# WaterDepthAnalysisBoardv2.net
KiCad netlist of a schematic drawn in Altium Designer
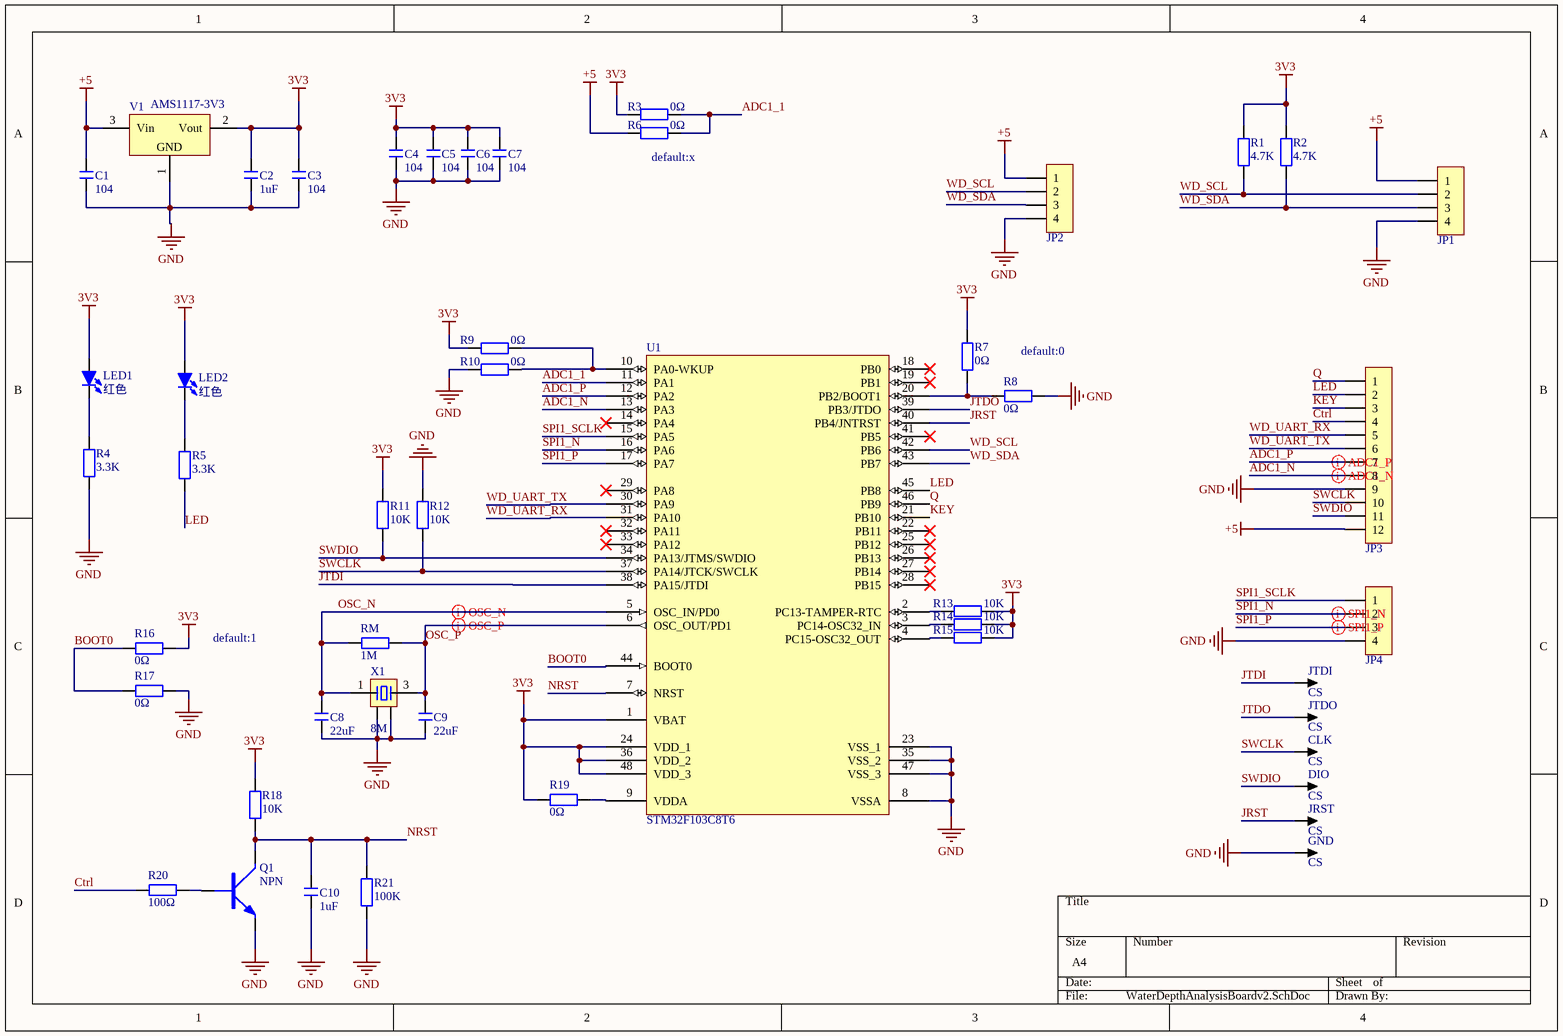
[diagram p0: WaterDepthAnalysisBoardv2.SchDoc]

(export (version "E")
  (design (tool "Eeschema 10.0.6"))
  (components
    (comp (ref "C1")
      (value "104")
      (footprint "C 0603_L")
      (description "无极性贴片电容")
      (fields (field (name "版权归属") "源创客"))
      (libsource (lib "3.1   - 电阻-电容-电感") (part "C"))
    )
    (comp (ref "C2")
      (value "1uF")
      (footprint "C 0603_L")
      (description "无极性贴片电容")
      (fields (field (name "版权归属") "源创客"))
      (libsource (lib "3.1   - 电阻-电容-电感") (part "C"))
    )
    (comp (ref "C3")
      (value "104")
      (footprint "C 0603_L")
      (description "无极性贴片电容")
      (fields (field (name "版权归属") "源创客"))
      (libsource (lib "3.1   - 电阻-电容-电感") (part "C"))
    )
    (comp (ref "C4")
      (value "104")
      (footprint "C 0603_L")
      (description "无极性贴片电容")
      (fields (field (name "版权归属") "源创客"))
      (libsource (lib "3.1   - 电阻-电容-电感") (part "C"))
    )
    (comp (ref "C5")
      (value "104")
      (footprint "C 0603_L")
      (description "无极性贴片电容")
      (fields (field (name "版权归属") "源创客"))
      (libsource (lib "3.1   - 电阻-电容-电感") (part "C"))
    )
    (comp (ref "C6")
      (value "104")
      (footprint "C 0603_L")
      (description "无极性贴片电容")
      (fields (field (name "版权归属") "源创客"))
      (libsource (lib "3.1   - 电阻-电容-电感") (part "C"))
    )
    (comp (ref "C7")
      (value "104")
      (footprint "C 0603_L")
      (description "无极性贴片电容")
      (fields (field (name "版权归属") "源创客"))
      (libsource (lib "3.1   - 电阻-电容-电感") (part "C"))
    )
    (comp (ref "C8")
      (value "22uF")
      (footprint "C 0603_L")
      (description "无极性贴片电容")
      (fields (field (name "版权归属") "源创客"))
      (libsource (lib "3.1   - 电阻-电容-电感") (part "C"))
    )
    (comp (ref "C9")
      (value "22uF")
      (footprint "C 0603_L")
      (description "无极性贴片电容")
      (fields (field (name "版权归属") "源创客"))
      (libsource (lib "3.1   - 电阻-电容-电感") (part "C"))
    )
    (comp (ref "C10")
      (value "1uF")
      (footprint "C 0603_L")
      (description "无极性贴片电容")
      (fields (field (name "版权归属") "源创客"))
      (libsource (lib "3.1   - 电阻-电容-电感") (part "C"))
    )
    (comp (ref "CLK")
      (value "CS")
      (footprint "R100")
      (description "探针焊盘")
      (fields (field (name "版权归属") "源创客"))
      (libsource (lib "15.1 - 未分类器件") (part "CS"))
    )
    (comp (ref "DIO")
      (value "CS")
      (footprint "R100")
      (description "探针焊盘")
      (fields (field (name "版权归属") "源创客"))
      (libsource (lib "15.1 - 未分类器件") (part "CS"))
    )
    (comp (ref "GND")
      (value "CS")
      (footprint "R100")
      (description "探针焊盘")
      (fields (field (name "版权归属") "源创客"))
      (libsource (lib "15.1 - 未分类器件") (part "CS"))
    )
    (comp (ref "JP1")
      (value "HDR-1X4")
      (footprint "MX 1.25-LI-4P")
      (description "4P接插件")
      (fields (field (name "版权归属") "源创客"))
      (libsource (lib "4.2   - 接插件-脚距1.25") (part "Header 4"))
    )
    (comp (ref "JP2")
      (value "HDR-1X4")
      (footprint "MX 1.25-LS-4P")
      (description "4P接插件")
      (fields (field (name "版权归属") "源创客"))
      (libsource (lib "4.2   - 接插件-脚距1.25") (part "Header 4"))
    )
    (comp (ref "JP3")
      (value "HDR-1X12")
      (footprint "HDR2.54-LI-12P")
      (description "12P接插件")
      (fields (field (name "版权归属") "源创客"))
      (libsource (lib "4.5   - 接插件-脚距2.54") (part "Header 12"))
    )
    (comp (ref "JP4")
      (value "HDR-1X4")
      (footprint "HDR2.54-LI-4P")
      (description "4P接插件")
      (fields (field (name "版权归属") "源创客"))
      (libsource (lib "4.5   - 接插件-脚距2.54") (part "Header 4"))
    )
    (comp (ref "JRST")
      (value "CS")
      (footprint "R100")
      (description "探针焊盘")
      (fields (field (name "版权归属") "源创客"))
      (libsource (lib "15.1 - 未分类器件") (part "CS"))
    )
    (comp (ref "JTDI")
      (value "CS")
      (footprint "R100")
      (description "探针焊盘")
      (fields (field (name "版权归属") "源创客"))
      (libsource (lib "15.1 - 未分类器件") (part "CS"))
    )
    (comp (ref "JTDO")
      (value "CS")
      (footprint "R100")
      (description "探针焊盘")
      (fields (field (name "版权归属") "源创客"))
      (libsource (lib "15.1 - 未分类器件") (part "CS"))
    )
    (comp (ref "LED1")
      (value "红色")
      (footprint "LED 0603W")
      (description "贴片LED")
      (fields (field (name "版权归属") "源创客"))
      (libsource (lib "9.1   - LED") (part "LED-SMD"))
    )
    (comp (ref "LED2")
      (value "红色")
      (footprint "LED 0603W")
      (description "贴片LED")
      (fields (field (name "版权归属") "源创客"))
      (libsource (lib "9.1   - LED") (part "LED-SMD"))
    )
    (comp (ref "Q1")
      (value "NPN")
      (footprint "SOT-23")
      (description "NPN三极管")
      (libsource (lib "三极管") (part "NPN"))
    )
    (comp (ref "R1")
      (value "4.7K")
      (footprint "R 0603_L")
      (description "贴片电阻")
      (fields (field (name "版权归属") "源创客"))
      (libsource (lib "3.1   - 电阻-电容-电感") (part "R"))
    )
    (comp (ref "R2")
      (value "4.7K")
      (footprint "R 0603_L")
      (description "贴片电阻")
      (fields (field (name "版权归属") "源创客"))
      (libsource (lib "3.1   - 电阻-电容-电感") (part "R"))
    )
    (comp (ref "R3")
      (value "0Ω")
      (footprint "R 0603_L")
      (description "贴片电阻")
      (fields (field (name "版权归属") "源创客"))
      (libsource (lib "3.1   - 电阻-电容-电感") (part "R"))
    )
    (comp (ref "R4")
      (value "3.3K")
      (footprint "R 0603_L")
      (description "贴片电阻")
      (fields (field (name "版权归属") "源创客"))
      (libsource (lib "3.1   - 电阻-电容-电感") (part "R"))
    )
    (comp (ref "R5")
      (value "3.3K")
      (footprint "R 0603_L")
      (description "贴片电阻")
      (fields (field (name "版权归属") "源创客"))
      (libsource (lib "3.1   - 电阻-电容-电感") (part "R"))
    )
    (comp (ref "R6")
      (value "0Ω")
      (footprint "R 0603_L")
      (description "贴片电阻")
      (fields (field (name "版权归属") "源创客"))
      (libsource (lib "3.1   - 电阻-电容-电感") (part "R"))
    )
    (comp (ref "R7")
      (value "0Ω")
      (footprint "R 0603_L")
      (description "贴片电阻")
      (fields (field (name "版权归属") "源创客"))
      (libsource (lib "3.1   - 电阻-电容-电感") (part "R"))
    )
    (comp (ref "R8")
      (value "0Ω")
      (footprint "R 0603_L")
      (description "贴片电阻")
      (fields (field (name "版权归属") "源创客"))
      (libsource (lib "3.1   - 电阻-电容-电感") (part "R"))
    )
    (comp (ref "R9")
      (value "0Ω")
      (footprint "R 0603_L")
      (description "贴片电阻")
      (fields (field (name "版权归属") "源创客"))
      (libsource (lib "3.1   - 电阻-电容-电感") (part "R"))
    )
    (comp (ref "R10")
      (value "0Ω")
      (footprint "R 0603_L")
      (description "贴片电阻")
      (fields (field (name "版权归属") "源创客"))
      (libsource (lib "3.1   - 电阻-电容-电感") (part "R"))
    )
    (comp (ref "R11")
      (value "10K")
      (footprint "R 0603_L")
      (description "贴片电阻")
      (fields (field (name "版权归属") "源创客"))
      (libsource (lib "3.1   - 电阻-电容-电感") (part "R"))
    )
    (comp (ref "R12")
      (value "10K")
      (footprint "R 0603_L")
      (description "贴片电阻")
      (fields (field (name "版权归属") "源创客"))
      (libsource (lib "3.1   - 电阻-电容-电感") (part "R"))
    )
    (comp (ref "R13")
      (value "10K")
      (footprint "R 0603_L")
      (description "贴片电阻")
      (fields (field (name "版权归属") "源创客"))
      (libsource (lib "3.1   - 电阻-电容-电感") (part "R"))
    )
    (comp (ref "R14")
      (value "10K")
      (footprint "R 0603_L")
      (description "贴片电阻")
      (fields (field (name "版权归属") "源创客"))
      (libsource (lib "3.1   - 电阻-电容-电感") (part "R"))
    )
    (comp (ref "R15")
      (value "10K")
      (footprint "R 0603_L")
      (description "贴片电阻")
      (fields (field (name "版权归属") "源创客"))
      (libsource (lib "3.1   - 电阻-电容-电感") (part "R"))
    )
    (comp (ref "R16")
      (value "0Ω")
      (footprint "R 0603_L")
      (description "贴片电阻")
      (fields (field (name "版权归属") "源创客"))
      (libsource (lib "3.1   - 电阻-电容-电感") (part "R"))
    )
    (comp (ref "R17")
      (value "0Ω")
      (footprint "R 0603_L")
      (description "贴片电阻")
      (fields (field (name "版权归属") "源创客"))
      (libsource (lib "3.1   - 电阻-电容-电感") (part "R"))
    )
    (comp (ref "R18")
      (value "10K")
      (footprint "R 0603_L")
      (description "贴片电阻")
      (fields (field (name "版权归属") "源创客"))
      (libsource (lib "3.1   - 电阻-电容-电感") (part "R"))
    )
    (comp (ref "R19")
      (value "0Ω")
      (footprint "R 0603_L")
      (description "贴片电阻")
      (fields (field (name "版权归属") "源创客"))
      (libsource (lib "3.1   - 电阻-电容-电感") (part "R"))
    )
    (comp (ref "R20")
      (value "100Ω")
      (footprint "R 0603_L")
      (description "贴片电阻")
      (fields (field (name "版权归属") "源创客"))
      (libsource (lib "3.1   - 电阻-电容-电感") (part "R"))
    )
    (comp (ref "R21")
      (value "100K")
      (footprint "R 0603_L")
      (description "贴片电阻")
      (fields (field (name "版权归属") "源创客"))
      (libsource (lib "3.1   - 电阻-电容-电感") (part "R"))
    )
    (comp (ref "RM")
      (value "1M")
      (footprint "R 0603_L")
      (description "贴片电阻")
      (fields (field (name "版权归属") "源创客"))
      (libsource (lib "3.1   - 电阻-电容-电感") (part "R"))
    )
    (comp (ref "U1")
      (value "STM32F103C8T6")
      (footprint "LQFP48 7X7")
      (libsource (lib "STM32系列") (part "STM32F103C8T6"))
    )
    (comp (ref "V1")
      (value "AMS1117-3V3")
      (footprint "SOT89_N")
      (description "三端稳压芯片")
      (fields (field (name "版权归属") "源创客"))
      (libsource (lib "1.3   - 电源类芯片") (part "AMS1117"))
    )
    (comp (ref "X1")
      (value "8M")
      (footprint "OSC 5032-4P")
      (description "4脚无源晶振")
      (fields (field (name "版权归属") "源创客"))
      (libsource (lib "10.1 - 保险丝-晶振") (part "XTAL-4P"))
    )
  )
  (nets
    (net (code "1") (name "+5") (class "Default")
      (node (ref "C1") (pin "2") (pinfunction "2_2") (pintype "passive"))
      (node (ref "JP1") (pin "1") (pinfunction "1_1") (pintype "passive"))
      (node (ref "JP2") (pin "1") (pinfunction "1_1") (pintype "passive"))
      (node (ref "JP3") (pin "12") (pinfunction "12_12") (pintype "passive"))
      (node (ref "R6") (pin "2") (pinfunction "2_2") (pintype "passive"))
      (node (ref "V1") (pin "3") (pinfunction "Vin_3") (pintype "passive"))
    )
    (net (code "2") (name "/ADC1_1") (class "Default")
      (node (ref "R3") (pin "1") (pinfunction "1_1") (pintype "passive"))
      (node (ref "R6") (pin "1") (pinfunction "1_1") (pintype "passive"))
      (node (ref "U1") (pin "11") (pinfunction "PA1_11") (pintype "bidirectional"))
    )
    (net (code "3") (name "/ADC1_N") (class "Default")
      (node (ref "JP3") (pin "8") (pinfunction "8_8") (pintype "passive"))
      (node (ref "U1") (pin "13") (pinfunction "PA3_13") (pintype "bidirectional"))
    )
    (net (code "4") (name "/ADC1_P") (class "Default")
      (node (ref "JP3") (pin "7") (pinfunction "7_7") (pintype "passive"))
      (node (ref "U1") (pin "12") (pinfunction "PA2_12") (pintype "bidirectional"))
    )
    (net (code "5") (name "/BOOT0") (class "Default")
      (node (ref "R16") (pin "2") (pinfunction "2_2") (pintype "passive"))
      (node (ref "R17") (pin "2") (pinfunction "2_2") (pintype "passive"))
      (node (ref "U1") (pin "44") (pinfunction "BOOT0_44") (pintype "input"))
    )
    (net (code "6") (name "/Ctrl") (class "Default")
      (node (ref "JP3") (pin "4") (pinfunction "4_4") (pintype "passive"))
      (node (ref "R20") (pin "2") (pinfunction "2_2") (pintype "passive"))
    )
    (net (code "7") (name "/JRST") (class "Default")
      (node (ref "JRST") (pin "1") (pinfunction "1_1") (pintype "passive"))
      (node (ref "U1") (pin "40") (pinfunction "PB4/JNTRST_40") (pintype "bidirectional"))
    )
    (net (code "8") (name "/JTDI") (class "Default")
      (node (ref "JTDI") (pin "1") (pinfunction "1_1") (pintype "passive"))
      (node (ref "U1") (pin "38") (pinfunction "PA15/JTDI_38") (pintype "bidirectional"))
    )
    (net (code "9") (name "/JTDO") (class "Default")
      (node (ref "JTDO") (pin "1") (pinfunction "1_1") (pintype "passive"))
      (node (ref "U1") (pin "39") (pinfunction "PB3/JTDO_39") (pintype "bidirectional"))
    )
    (net (code "10") (name "/KEY") (class "Default")
      (node (ref "JP3") (pin "3") (pinfunction "3_3") (pintype "passive"))
      (node (ref "U1") (pin "21") (pinfunction "PB10_21") (pintype "bidirectional"))
    )
    (net (code "11") (name "/LED") (class "Default")
      (node (ref "JP3") (pin "2") (pinfunction "2_2") (pintype "passive"))
      (node (ref "R5") (pin "1") (pinfunction "1_1") (pintype "passive"))
      (node (ref "U1") (pin "45") (pinfunction "PB8_45") (pintype "bidirectional"))
    )
    (net (code "12") (name "/NRST") (class "Default")
      (node (ref "C10") (pin "2") (pinfunction "2_2") (pintype "passive"))
      (node (ref "Q1") (pin "C") (pinfunction "C_C") (pintype "passive"))
      (node (ref "R18") (pin "2") (pinfunction "2_2") (pintype "passive"))
      (node (ref "R21") (pin "1") (pinfunction "1_1") (pintype "passive"))
      (node (ref "U1") (pin "7") (pinfunction "NRST_7") (pintype "bidirectional"))
    )
    (net (code "13") (name "/OSC_N") (class "Default")
      (node (ref "C8") (pin "2") (pinfunction "2_2") (pintype "passive"))
      (node (ref "RM") (pin "2") (pinfunction "2_2") (pintype "passive"))
      (node (ref "U1") (pin "5") (pinfunction "OSC_IN/PD0_5") (pintype "input"))
      (node (ref "X1") (pin "1") (pinfunction "1_1") (pintype "passive"))
    )
    (net (code "14") (name "/OSC_P") (class "Default")
      (node (ref "C9") (pin "2") (pinfunction "2_2") (pintype "passive"))
      (node (ref "RM") (pin "1") (pinfunction "1_1") (pintype "passive"))
      (node (ref "U1") (pin "6") (pinfunction "OSC_OUT/PD1_6") (pintype "output"))
      (node (ref "X1") (pin "3") (pinfunction "3_3") (pintype "passive"))
    )
    (net (code "15") (name "/Q") (class "Default")
      (node (ref "JP3") (pin "1") (pinfunction "1_1") (pintype "passive"))
      (node (ref "U1") (pin "46") (pinfunction "PB9_46") (pintype "bidirectional"))
    )
    (net (code "16") (name "/SPI1_N") (class "Default")
      (node (ref "JP4") (pin "2") (pinfunction "2_2") (pintype "passive"))
      (node (ref "U1") (pin "16") (pinfunction "PA6_16") (pintype "bidirectional"))
    )
    (net (code "17") (name "/SPI1_P") (class "Default")
      (node (ref "JP4") (pin "3") (pinfunction "3_3") (pintype "passive"))
      (node (ref "U1") (pin "17") (pinfunction "PA7_17") (pintype "bidirectional"))
    )
    (net (code "18") (name "/SPI1_SCLK") (class "Default")
      (node (ref "JP4") (pin "1") (pinfunction "1_1") (pintype "passive"))
      (node (ref "U1") (pin "15") (pinfunction "PA5_15") (pintype "bidirectional"))
    )
    (net (code "19") (name "/SWCLK") (class "Default")
      (node (ref "CLK") (pin "1") (pinfunction "1_1") (pintype "passive"))
      (node (ref "JP3") (pin "10") (pinfunction "10_10") (pintype "passive"))
      (node (ref "R12") (pin "2") (pinfunction "2_2") (pintype "passive"))
      (node (ref "U1") (pin "37") (pinfunction "PA14/JTCK/SWCLK_37") (pintype "bidirectional"))
    )
    (net (code "20") (name "/SWDIO") (class "Default")
      (node (ref "DIO") (pin "1") (pinfunction "1_1") (pintype "passive"))
      (node (ref "JP3") (pin "11") (pinfunction "11_11") (pintype "passive"))
      (node (ref "R11") (pin "2") (pinfunction "2_2") (pintype "passive"))
      (node (ref "U1") (pin "34") (pinfunction "PA13/JTMS/SWDIO_34") (pintype "bidirectional"))
    )
    (net (code "21") (name "/WD_SCL") (class "Default")
      (node (ref "JP1") (pin "2") (pinfunction "2_2") (pintype "passive"))
      (node (ref "JP2") (pin "2") (pinfunction "2_2") (pintype "passive"))
      (node (ref "R1") (pin "1") (pinfunction "1_1") (pintype "passive"))
      (node (ref "U1") (pin "42") (pinfunction "PB6_42") (pintype "bidirectional"))
    )
    (net (code "22") (name "/WD_SDA") (class "Default")
      (node (ref "JP1") (pin "3") (pinfunction "3_3") (pintype "passive"))
      (node (ref "JP2") (pin "3") (pinfunction "3_3") (pintype "passive"))
      (node (ref "R2") (pin "1") (pinfunction "1_1") (pintype "passive"))
      (node (ref "U1") (pin "43") (pinfunction "PB7_43") (pintype "bidirectional"))
    )
    (net (code "23") (name "/WD_UART_RX") (class "Default")
      (node (ref "JP3") (pin "5") (pinfunction "5_5") (pintype "passive"))
      (node (ref "U1") (pin "31") (pinfunction "PA10_31") (pintype "bidirectional"))
    )
    (net (code "24") (name "/WD_UART_TX") (class "Default")
      (node (ref "JP3") (pin "6") (pinfunction "6_6") (pintype "passive"))
      (node (ref "U1") (pin "30") (pinfunction "PA9_30") (pintype "bidirectional"))
    )
    (net (code "25") (name "3V3") (class "Default")
      (node (ref "C2") (pin "2") (pinfunction "2_2") (pintype "passive"))
      (node (ref "C3") (pin "2") (pinfunction "2_2") (pintype "passive"))
      (node (ref "C4") (pin "2") (pinfunction "2_2") (pintype "passive"))
      (node (ref "C5") (pin "2") (pinfunction "2_2") (pintype "passive"))
      (node (ref "C6") (pin "2") (pinfunction "2_2") (pintype "passive"))
      (node (ref "C7") (pin "2") (pinfunction "2_2") (pintype "passive"))
      (node (ref "LED1") (pin "1") (pinfunction "A_1") (pintype "passive"))
      (node (ref "LED2") (pin "1") (pinfunction "A_1") (pintype "passive"))
      (node (ref "R1") (pin "2") (pinfunction "2_2") (pintype "passive"))
      (node (ref "R11") (pin "1") (pinfunction "1_1") (pintype "passive"))
      (node (ref "R13") (pin "1") (pinfunction "1_1") (pintype "passive"))
      (node (ref "R14") (pin "1") (pinfunction "1_1") (pintype "passive"))
      (node (ref "R15") (pin "1") (pinfunction "1_1") (pintype "passive"))
      (node (ref "R16") (pin "1") (pinfunction "1_1") (pintype "passive"))
      (node (ref "R18") (pin "1") (pinfunction "1_1") (pintype "passive"))
      (node (ref "R19") (pin "2") (pinfunction "2_2") (pintype "passive"))
      (node (ref "R2") (pin "2") (pinfunction "2_2") (pintype "passive"))
      (node (ref "R3") (pin "2") (pinfunction "2_2") (pintype "passive"))
      (node (ref "R7") (pin "1") (pinfunction "1_1") (pintype "passive"))
      (node (ref "R9") (pin "2") (pinfunction "2_2") (pintype "passive"))
      (node (ref "U1") (pin "1") (pinfunction "VBAT_1") (pintype "power_in"))
      (node (ref "U1") (pin "24") (pinfunction "VDD_1_24") (pintype "power_in"))
      (node (ref "U1") (pin "36") (pinfunction "VDD_2_36") (pintype "power_in"))
      (node (ref "U1") (pin "48") (pinfunction "VDD_3_48") (pintype "power_in"))
      (node (ref "V1") (pin "2") (pinfunction "Vout_2") (pintype "passive"))
    )
    (net (code "26") (name "GND") (class "Default")
      (node (ref "C1") (pin "1") (pinfunction "1_1") (pintype "passive"))
      (node (ref "C10") (pin "1") (pinfunction "1_1") (pintype "passive"))
      (node (ref "C2") (pin "1") (pinfunction "1_1") (pintype "passive"))
      (node (ref "C3") (pin "1") (pinfunction "1_1") (pintype "passive"))
      (node (ref "C4") (pin "1") (pinfunction "1_1") (pintype "passive"))
      (node (ref "C5") (pin "1") (pinfunction "1_1") (pintype "passive"))
      (node (ref "C6") (pin "1") (pinfunction "1_1") (pintype "passive"))
      (node (ref "C7") (pin "1") (pinfunction "1_1") (pintype "passive"))
      (node (ref "C8") (pin "1") (pinfunction "1_1") (pintype "passive"))
      (node (ref "C9") (pin "1") (pinfunction "1_1") (pintype "passive"))
      (node (ref "GND") (pin "1") (pinfunction "1_1") (pintype "passive"))
      (node (ref "JP1") (pin "4") (pinfunction "4_4") (pintype "passive"))
      (node (ref "JP2") (pin "4") (pinfunction "4_4") (pintype "passive"))
      (node (ref "JP3") (pin "9") (pinfunction "9_9") (pintype "passive"))
      (node (ref "JP4") (pin "4") (pinfunction "4_4") (pintype "passive"))
      (node (ref "Q1") (pin "E") (pinfunction "E_E") (pintype "passive"))
      (node (ref "R10") (pin "2") (pinfunction "2_2") (pintype "passive"))
      (node (ref "R12") (pin "1") (pinfunction "1_1") (pintype "passive"))
      (node (ref "R17") (pin "1") (pinfunction "1_1") (pintype "passive"))
      (node (ref "R21") (pin "2") (pinfunction "2_2") (pintype "passive"))
      (node (ref "R4") (pin "1") (pinfunction "1_1") (pintype "passive"))
      (node (ref "R8") (pin "1") (pinfunction "1_1") (pintype "passive"))
      (node (ref "U1") (pin "23") (pinfunction "VSS_1_23") (pintype "power_in"))
      (node (ref "U1") (pin "35") (pinfunction "VSS_2_35") (pintype "power_in"))
      (node (ref "U1") (pin "47") (pinfunction "VSS_3_47") (pintype "power_in"))
      (node (ref "U1") (pin "8") (pinfunction "VSSA_8") (pintype "power_in"))
      (node (ref "V1") (pin "1") (pinfunction "GND_1") (pintype "passive"))
      (node (ref "X1") (pin "2") (pinfunction "2_2") (pintype "passive"))
      (node (ref "X1") (pin "4") (pinfunction "4_4") (pintype "passive"))
    )
    (net (code "27") (name "Net-(LED1-K)") (class "Default")
      (node (ref "LED1") (pin "2") (pinfunction "K_2") (pintype "passive"))
      (node (ref "R4") (pin "2") (pinfunction "2_2") (pintype "passive"))
    )
    (net (code "28") (name "Net-(LED2-K)") (class "Default")
      (node (ref "LED2") (pin "2") (pinfunction "K_2") (pintype "passive"))
      (node (ref "R5") (pin "2") (pinfunction "2_2") (pintype "passive"))
    )
    (net (code "29") (name "Net-(Q1-PadB)") (class "Default")
      (node (ref "Q1") (pin "B") (pinfunction "B_B") (pintype "passive"))
      (node (ref "R20") (pin "1") (pinfunction "1_1") (pintype "passive"))
    )
    (net (code "30") (name "Net-(U1-PA0-WKUP)") (class "Default")
      (node (ref "R10") (pin "1") (pinfunction "1_1") (pintype "passive"))
      (node (ref "R9") (pin "1") (pinfunction "1_1") (pintype "passive"))
      (node (ref "U1") (pin "10") (pinfunction "PA0-WKUP_10") (pintype "bidirectional"))
    )
    (net (code "31") (name "Net-(U1-PB2{slash}BOOT1)") (class "Default")
      (node (ref "R7") (pin "2") (pinfunction "2_2") (pintype "passive"))
      (node (ref "R8") (pin "2") (pinfunction "2_2") (pintype "passive"))
      (node (ref "U1") (pin "20") (pinfunction "PB2/BOOT1_20") (pintype "bidirectional"))
    )
    (net (code "32") (name "Net-(U1-PC13-TAMPER-RTC)") (class "Default")
      (node (ref "R13") (pin "2") (pinfunction "2_2") (pintype "passive"))
      (node (ref "U1") (pin "2") (pinfunction "PC13-TAMPER-RTC_2") (pintype "bidirectional"))
    )
    (net (code "33") (name "Net-(U1-PC14-OSC32_IN)") (class "Default")
      (node (ref "R14") (pin "2") (pinfunction "2_2") (pintype "passive"))
      (node (ref "U1") (pin "3") (pinfunction "PC14-OSC32_IN_3") (pintype "bidirectional"))
    )
    (net (code "34") (name "Net-(U1-PC15-OSC32_OUT)") (class "Default")
      (node (ref "R15") (pin "2") (pinfunction "2_2") (pintype "passive"))
      (node (ref "U1") (pin "4") (pinfunction "PC15-OSC32_OUT_4") (pintype "bidirectional"))
    )
    (net (code "35") (name "Net-(U1-VDDA)") (class "Default")
      (node (ref "R19") (pin "1") (pinfunction "1_1") (pintype "passive"))
      (node (ref "U1") (pin "9") (pinfunction "VDDA_9") (pintype "power_in"))
    )
    (net (code "36") (name "unconnected-(U1-PA4-Pad14)") (class "Default")
      (node (ref "U1") (pin "14") (pinfunction "PA4_14") (pintype "bidirectional+no_connect"))
    )
    (net (code "37") (name "unconnected-(U1-PA8-Pad29)") (class "Default")
      (node (ref "U1") (pin "29") (pinfunction "PA8_29") (pintype "bidirectional+no_connect"))
    )
    (net (code "38") (name "unconnected-(U1-PA11-Pad32)") (class "Default")
      (node (ref "U1") (pin "32") (pinfunction "PA11_32") (pintype "bidirectional+no_connect"))
    )
    (net (code "39") (name "unconnected-(U1-PA12-Pad33)") (class "Default")
      (node (ref "U1") (pin "33") (pinfunction "PA12_33") (pintype "bidirectional+no_connect"))
    )
    (net (code "40") (name "unconnected-(U1-PB0-Pad18)") (class "Default")
      (node (ref "U1") (pin "18") (pinfunction "PB0_18") (pintype "bidirectional+no_connect"))
    )
    (net (code "41") (name "unconnected-(U1-PB1-Pad19)") (class "Default")
      (node (ref "U1") (pin "19") (pinfunction "PB1_19") (pintype "bidirectional+no_connect"))
    )
    (net (code "42") (name "unconnected-(U1-PB5-Pad41)") (class "Default")
      (node (ref "U1") (pin "41") (pinfunction "PB5_41") (pintype "bidirectional+no_connect"))
    )
    (net (code "43") (name "unconnected-(U1-PB11-Pad22)") (class "Default")
      (node (ref "U1") (pin "22") (pinfunction "PB11_22") (pintype "bidirectional+no_connect"))
    )
    (net (code "44") (name "unconnected-(U1-PB12-Pad25)") (class "Default")
      (node (ref "U1") (pin "25") (pinfunction "PB12_25") (pintype "bidirectional+no_connect"))
    )
    (net (code "45") (name "unconnected-(U1-PB13-Pad26)") (class "Default")
      (node (ref "U1") (pin "26") (pinfunction "PB13_26") (pintype "bidirectional+no_connect"))
    )
    (net (code "46") (name "unconnected-(U1-PB14-Pad27)") (class "Default")
      (node (ref "U1") (pin "27") (pinfunction "PB14_27") (pintype "bidirectional+no_connect"))
    )
    (net (code "47") (name "unconnected-(U1-PB15-Pad28)") (class "Default")
      (node (ref "U1") (pin "28") (pinfunction "PB15_28") (pintype "bidirectional+no_connect"))
    )
  )
)
